# RS232_to_TTL_Converter_MAX3232IDR.net
KiCad netlist of a schematic drawn in EAGLE
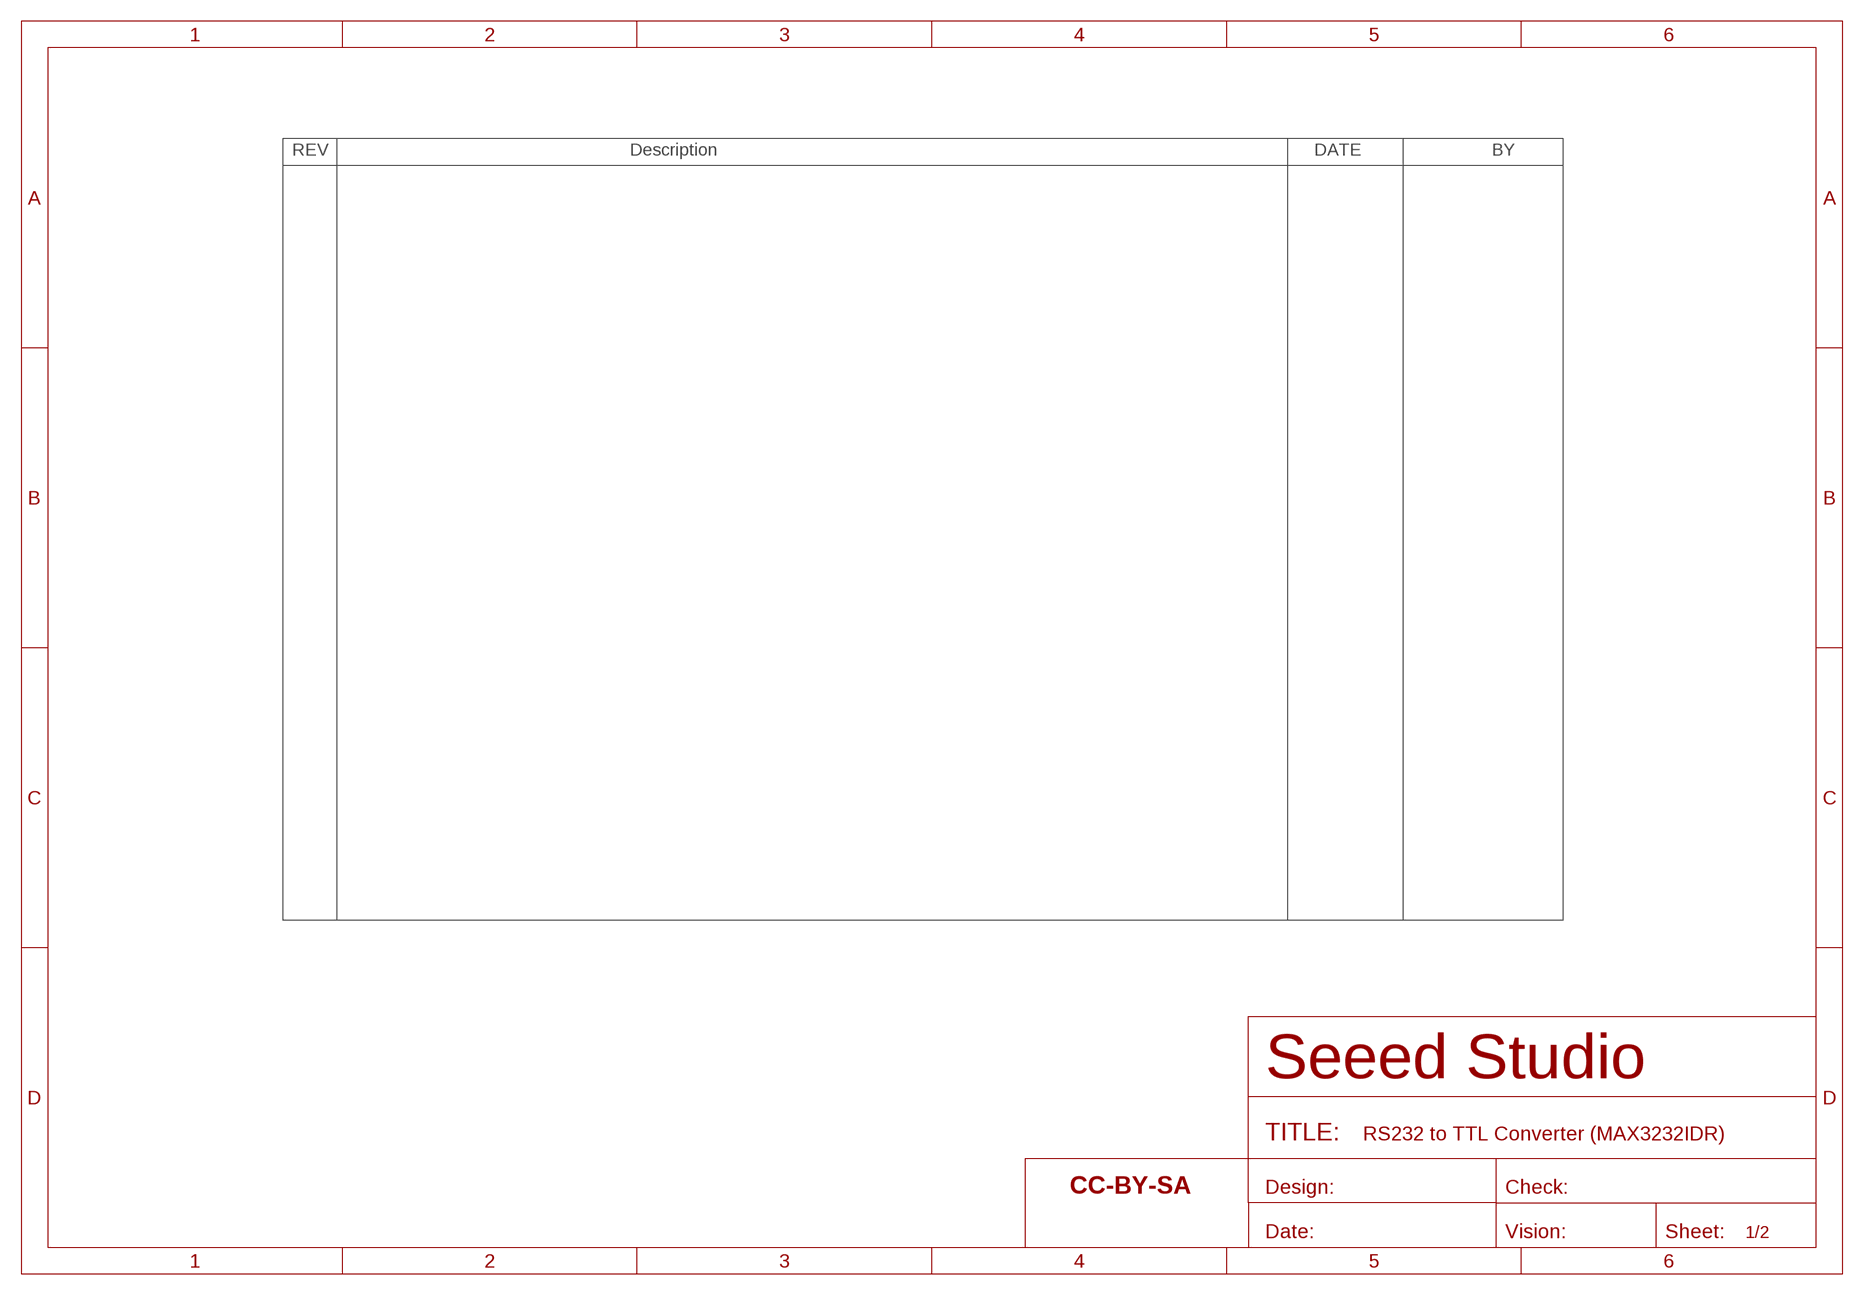
[diagram p0: schematic, sheet 1]
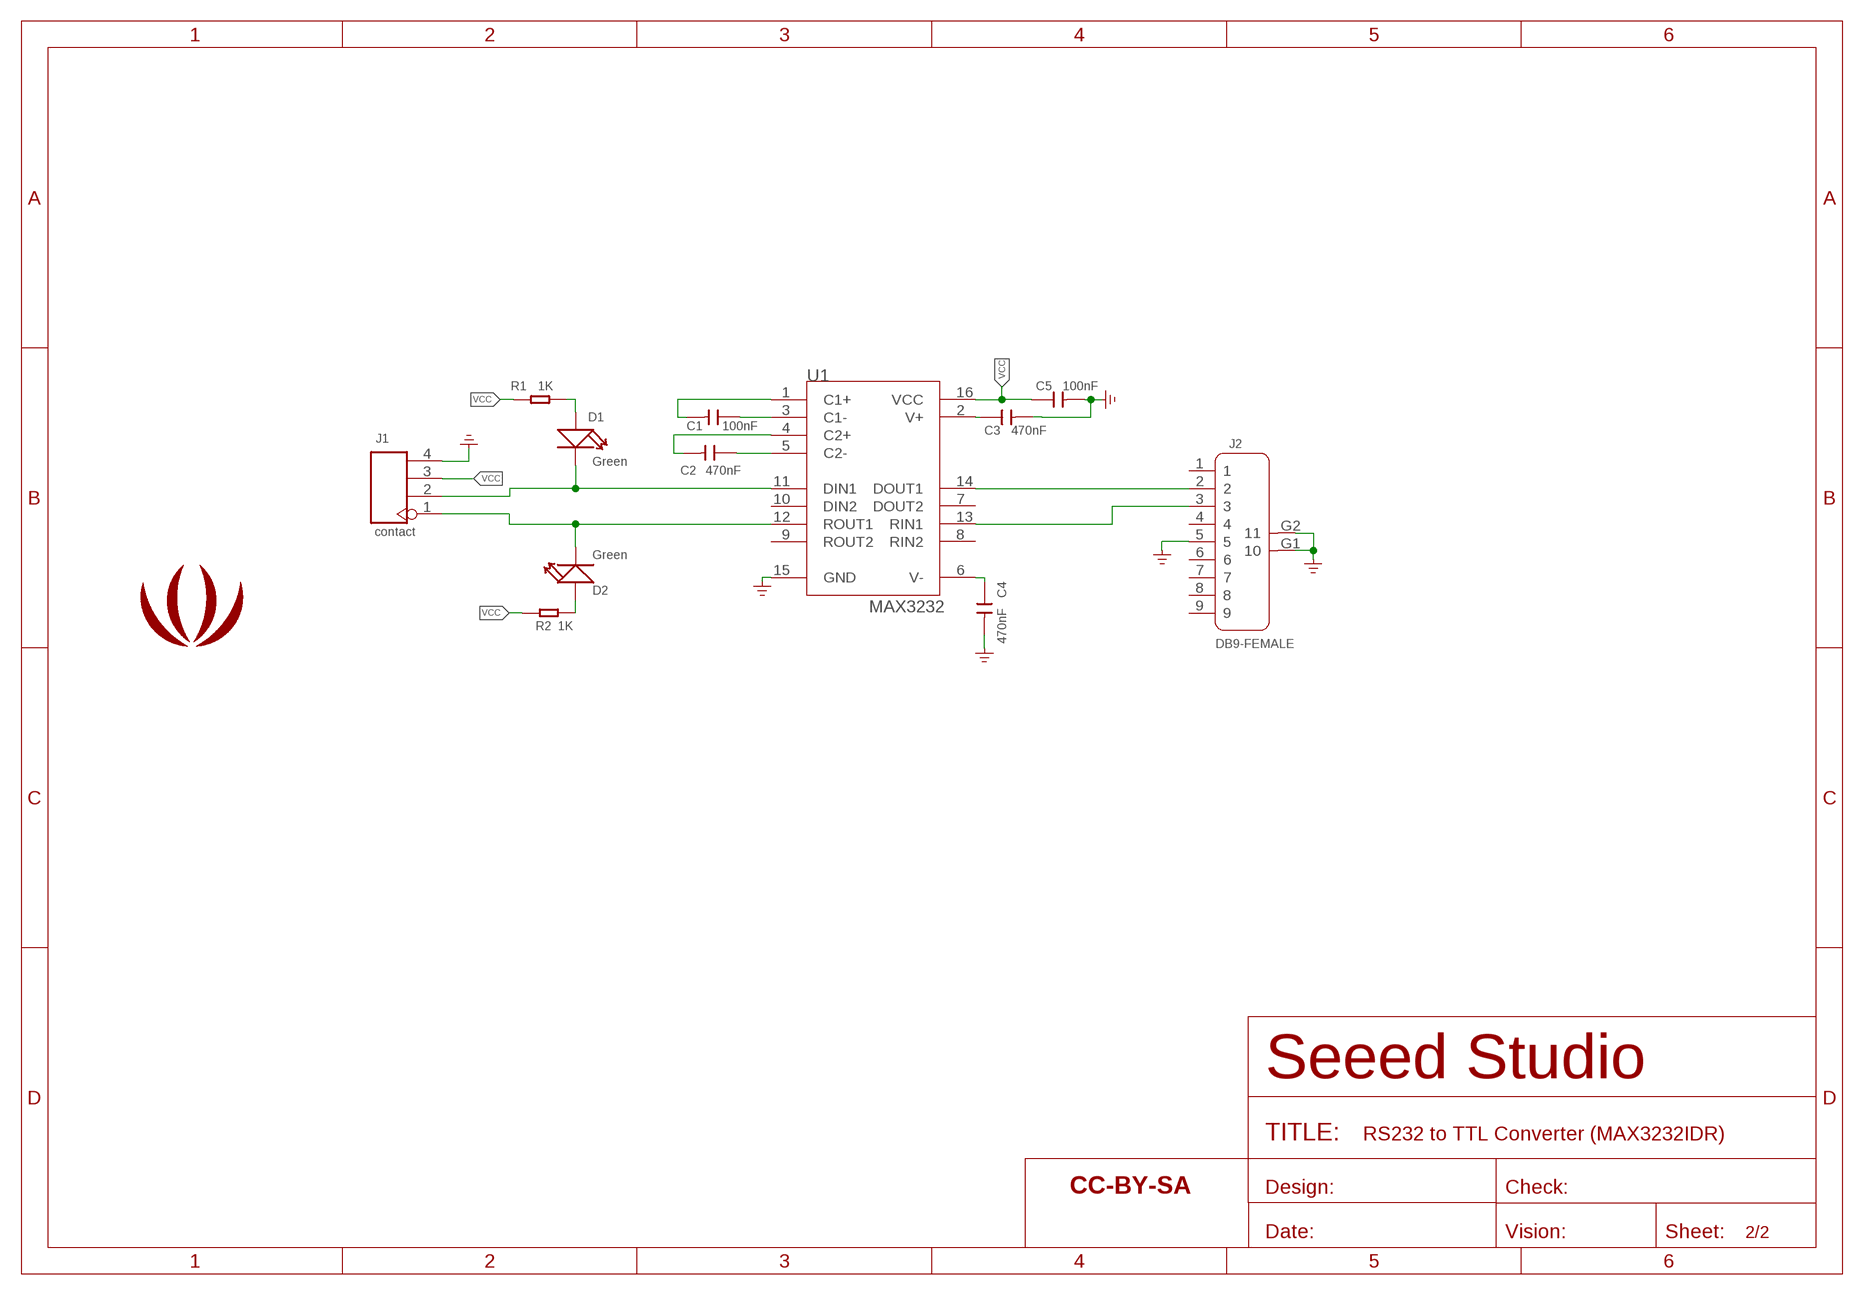
[diagram p1: schematic, sheet 2]

(export (version "E")
  (design (tool "Eeschema 10.0.6"))
  (components
    (comp (ref "FR1")
      (value "SEEEDSTUDIO-OPEN-SCH-FRAME")
      (footprint "eagle-import:SEEEDSTUDIO-PCB-FRAME")
      (libsource (lib "eagle-import") (part "SEEEDSTUDIO-OPEN-SCH-FRAME"))
    )
    (comp (ref "C1")
      (value "100nF")
      (footprint "eagle-import:C0603")
      (libsource (lib "eagle-import") (part "CAP-0603"))
    )
    (comp (ref "C2")
      (value "470nF")
      (footprint "eagle-import:C0603")
      (libsource (lib "eagle-import") (part "CAP-0603"))
    )
    (comp (ref "C3")
      (value "470nF")
      (footprint "eagle-import:C0603")
      (libsource (lib "eagle-import") (part "CAP-0603"))
    )
    (comp (ref "C4")
      (value "470nF")
      (footprint "eagle-import:C0603")
      (libsource (lib "eagle-import") (part "CAP-0603"))
    )
    (comp (ref "C5")
      (value "100nF")
      (footprint "eagle-import:C0603")
      (libsource (lib "eagle-import") (part "CAP-0603"))
    )
    (comp (ref "D1")
      (value "Green")
      (footprint "eagle-import:LED-0603")
      (libsource (lib "eagle-import") (part "LED'0603'"))
    )
    (comp (ref "D2")
      (value "Green")
      (footprint "eagle-import:LED-0603")
      (libsource (lib "eagle-import") (part "LED'0603'"))
    )
    (comp (ref "FR2")
      (value "SEEEDSTUDIO-OPEN-SCH-FRAME")
      (footprint "eagle-import:SEEEDSTUDIO-PCB-FRAME")
      (libsource (lib "eagle-import") (part "SEEEDSTUDIO-OPEN-SCH-FRAME"))
    )
    (comp (ref "J1")
      (value "contact")
      (footprint "eagle-import:H4-2.54")
      (libsource (lib "eagle-import") (part "HEADER-4P-65/35MIL"))
    )
    (comp (ref "J2")
      (value "DB9-FEMALE")
      (footprint "eagle-import:DSUB9+2P-2.77-90D-FEMALE")
      (libsource (lib "eagle-import") (part "DSUB-CONNECTOR-9'FEMAL'"))
    )
    (comp (ref "R1")
      (value "1K")
      (footprint "eagle-import:R0603")
      (libsource (lib "eagle-import") (part "RES-0603"))
    )
    (comp (ref "R2")
      (value "1K")
      (footprint "eagle-import:R0603")
      (libsource (lib "eagle-import") (part "RES-0603"))
    )
    (comp (ref "U$2")
      (value "LOGO-SEEED-BIG-SILK")
      (footprint "eagle-import:SEEED-SILK-280_268MIL")
      (fields (field (name "PARTNO") "DNP"))
      (libsource (lib "eagle-import") (part "LOGO-SEEED-BIG-SILK"))
    )
    (comp (ref "U1")
      (value "MAX3232")
      (footprint "eagle-import:SOIC16-1.27-10X3.9MM")
      (libsource (lib "eagle-import") (part "RF-MAX232D"))
    )
  )
  (nets
    (net (code "1") (name "GND") (class "Default")
      (node (ref "C3") (pin "2") (pinfunction "2_2") (pintype "passive"))
      (node (ref "C4") (pin "2") (pinfunction "2_2") (pintype "passive"))
      (node (ref "C5") (pin "2") (pinfunction "2_2") (pintype "passive"))
      (node (ref "J1") (pin "4") (pinfunction "P$4_4") (pintype "bidirectional"))
      (node (ref "J2") (pin "5") (pinfunction "5_5") (pintype "bidirectional"))
      (node (ref "J2") (pin "G1") (pinfunction "10_G1") (pintype "bidirectional"))
      (node (ref "J2") (pin "G2") (pinfunction "11_G2") (pintype "bidirectional"))
      (node (ref "U1") (pin "15") (pinfunction "GND_15") (pintype "bidirectional"))
    )
    (net (code "2") (name "Net-(D1-Pad+)") (class "Default")
      (node (ref "D1") (pin "+") (pinfunction "+_+") (pintype "passive"))
      (node (ref "R1") (pin "1") (pinfunction "1_1") (pintype "passive"))
    )
    (net (code "3") (name "Net-(D2-Pad+)") (class "Default")
      (node (ref "D2") (pin "+") (pinfunction "+_+") (pintype "passive"))
      (node (ref "R2") (pin "2") (pinfunction "2_2") (pintype "passive"))
    )
    (net (code "4") (name "Net-(J1-P$1)") (class "Default")
      (node (ref "D2") (pin "-") (pinfunction "-_-") (pintype "passive"))
      (node (ref "J1") (pin "1") (pinfunction "P$1_1") (pintype "bidirectional"))
      (node (ref "U1") (pin "12") (pinfunction "ROUT1_12") (pintype "bidirectional"))
    )
    (net (code "5") (name "Net-(J1-P$2)") (class "Default")
      (node (ref "D1") (pin "-") (pinfunction "-_-") (pintype "passive"))
      (node (ref "J1") (pin "2") (pinfunction "P$2_2") (pintype "bidirectional"))
      (node (ref "U1") (pin "11") (pinfunction "DIN1_11") (pintype "input"))
    )
    (net (code "6") (name "Net-(U1-C1+)") (class "Default")
      (node (ref "C1") (pin "2") (pinfunction "2_2") (pintype "passive"))
      (node (ref "U1") (pin "1") (pinfunction "C1+_1") (pintype "bidirectional"))
    )
    (net (code "7") (name "Net-(U1-C1-)") (class "Default")
      (node (ref "C1") (pin "1") (pinfunction "1_1") (pintype "passive"))
      (node (ref "U1") (pin "3") (pinfunction "C1-_3") (pintype "bidirectional"))
    )
    (net (code "8") (name "Net-(U1-C2+)") (class "Default")
      (node (ref "C2") (pin "2") (pinfunction "2_2") (pintype "passive"))
      (node (ref "U1") (pin "4") (pinfunction "C2+_4") (pintype "bidirectional"))
    )
    (net (code "9") (name "Net-(U1-C2-)") (class "Default")
      (node (ref "C2") (pin "1") (pinfunction "1_1") (pintype "passive"))
      (node (ref "U1") (pin "5") (pinfunction "C2-_5") (pintype "bidirectional"))
    )
    (net (code "10") (name "Net-(U1-DOUT1)") (class "Default")
      (node (ref "J2") (pin "2") (pinfunction "2_2") (pintype "bidirectional"))
      (node (ref "U1") (pin "14") (pinfunction "DOUT1_14") (pintype "bidirectional"))
    )
    (net (code "11") (name "Net-(U1-RIN1)") (class "Default")
      (node (ref "J2") (pin "3") (pinfunction "3_3") (pintype "bidirectional"))
      (node (ref "U1") (pin "13") (pinfunction "RIN1_13") (pintype "bidirectional"))
    )
    (net (code "12") (name "Net-(U1-V+)") (class "Default")
      (node (ref "C3") (pin "1") (pinfunction "1_1") (pintype "passive"))
      (node (ref "U1") (pin "2") (pinfunction "V+_2") (pintype "bidirectional"))
    )
    (net (code "13") (name "Net-(U1-V-)") (class "Default")
      (node (ref "C4") (pin "1") (pinfunction "1_1") (pintype "passive"))
      (node (ref "U1") (pin "6") (pinfunction "V-_6") (pintype "bidirectional"))
    )
    (net (code "14") (name "VCC") (class "Default")
      (node (ref "C5") (pin "1") (pinfunction "1_1") (pintype "passive"))
      (node (ref "J1") (pin "3") (pinfunction "P$3_3") (pintype "bidirectional"))
      (node (ref "R1") (pin "2") (pinfunction "2_2") (pintype "passive"))
      (node (ref "R2") (pin "1") (pinfunction "1_1") (pintype "passive"))
      (node (ref "U1") (pin "16") (pinfunction "VCC_16") (pintype "bidirectional"))
    )
    (net (code "15") (name "unconnected-(J2-Pad1)") (class "Default")
      (node (ref "J2") (pin "1") (pinfunction "1_1") (pintype "bidirectional"))
    )
    (net (code "16") (name "unconnected-(J2-Pad4)") (class "Default")
      (node (ref "J2") (pin "4") (pinfunction "4_4") (pintype "bidirectional"))
    )
    (net (code "17") (name "unconnected-(J2-Pad6)") (class "Default")
      (node (ref "J2") (pin "6") (pinfunction "6_6") (pintype "bidirectional"))
    )
    (net (code "18") (name "unconnected-(J2-Pad7)") (class "Default")
      (node (ref "J2") (pin "7") (pinfunction "7_7") (pintype "bidirectional"))
    )
    (net (code "19") (name "unconnected-(J2-Pad8)") (class "Default")
      (node (ref "J2") (pin "8") (pinfunction "8_8") (pintype "bidirectional"))
    )
    (net (code "20") (name "unconnected-(J2-Pad9)") (class "Default")
      (node (ref "J2") (pin "9") (pinfunction "9_9") (pintype "bidirectional"))
    )
    (net (code "21") (name "unconnected-(U1-DIN2-Pad10)") (class "Default")
      (node (ref "U1") (pin "10") (pinfunction "DIN2_10") (pintype "bidirectional"))
    )
    (net (code "22") (name "unconnected-(U1-DOUT2-Pad7)") (class "Default")
      (node (ref "U1") (pin "7") (pinfunction "DOUT2_7") (pintype "bidirectional"))
    )
    (net (code "23") (name "unconnected-(U1-RIN2-Pad8)") (class "Default")
      (node (ref "U1") (pin "8") (pinfunction "RIN2_8") (pintype "bidirectional"))
    )
    (net (code "24") (name "unconnected-(U1-ROUT2-Pad9)") (class "Default")
      (node (ref "U1") (pin "9") (pinfunction "ROUT2_9") (pintype "bidirectional"))
    )
  )
)
